# Sheet1.net
KiCad netlist of a schematic drawn in Altium Designer
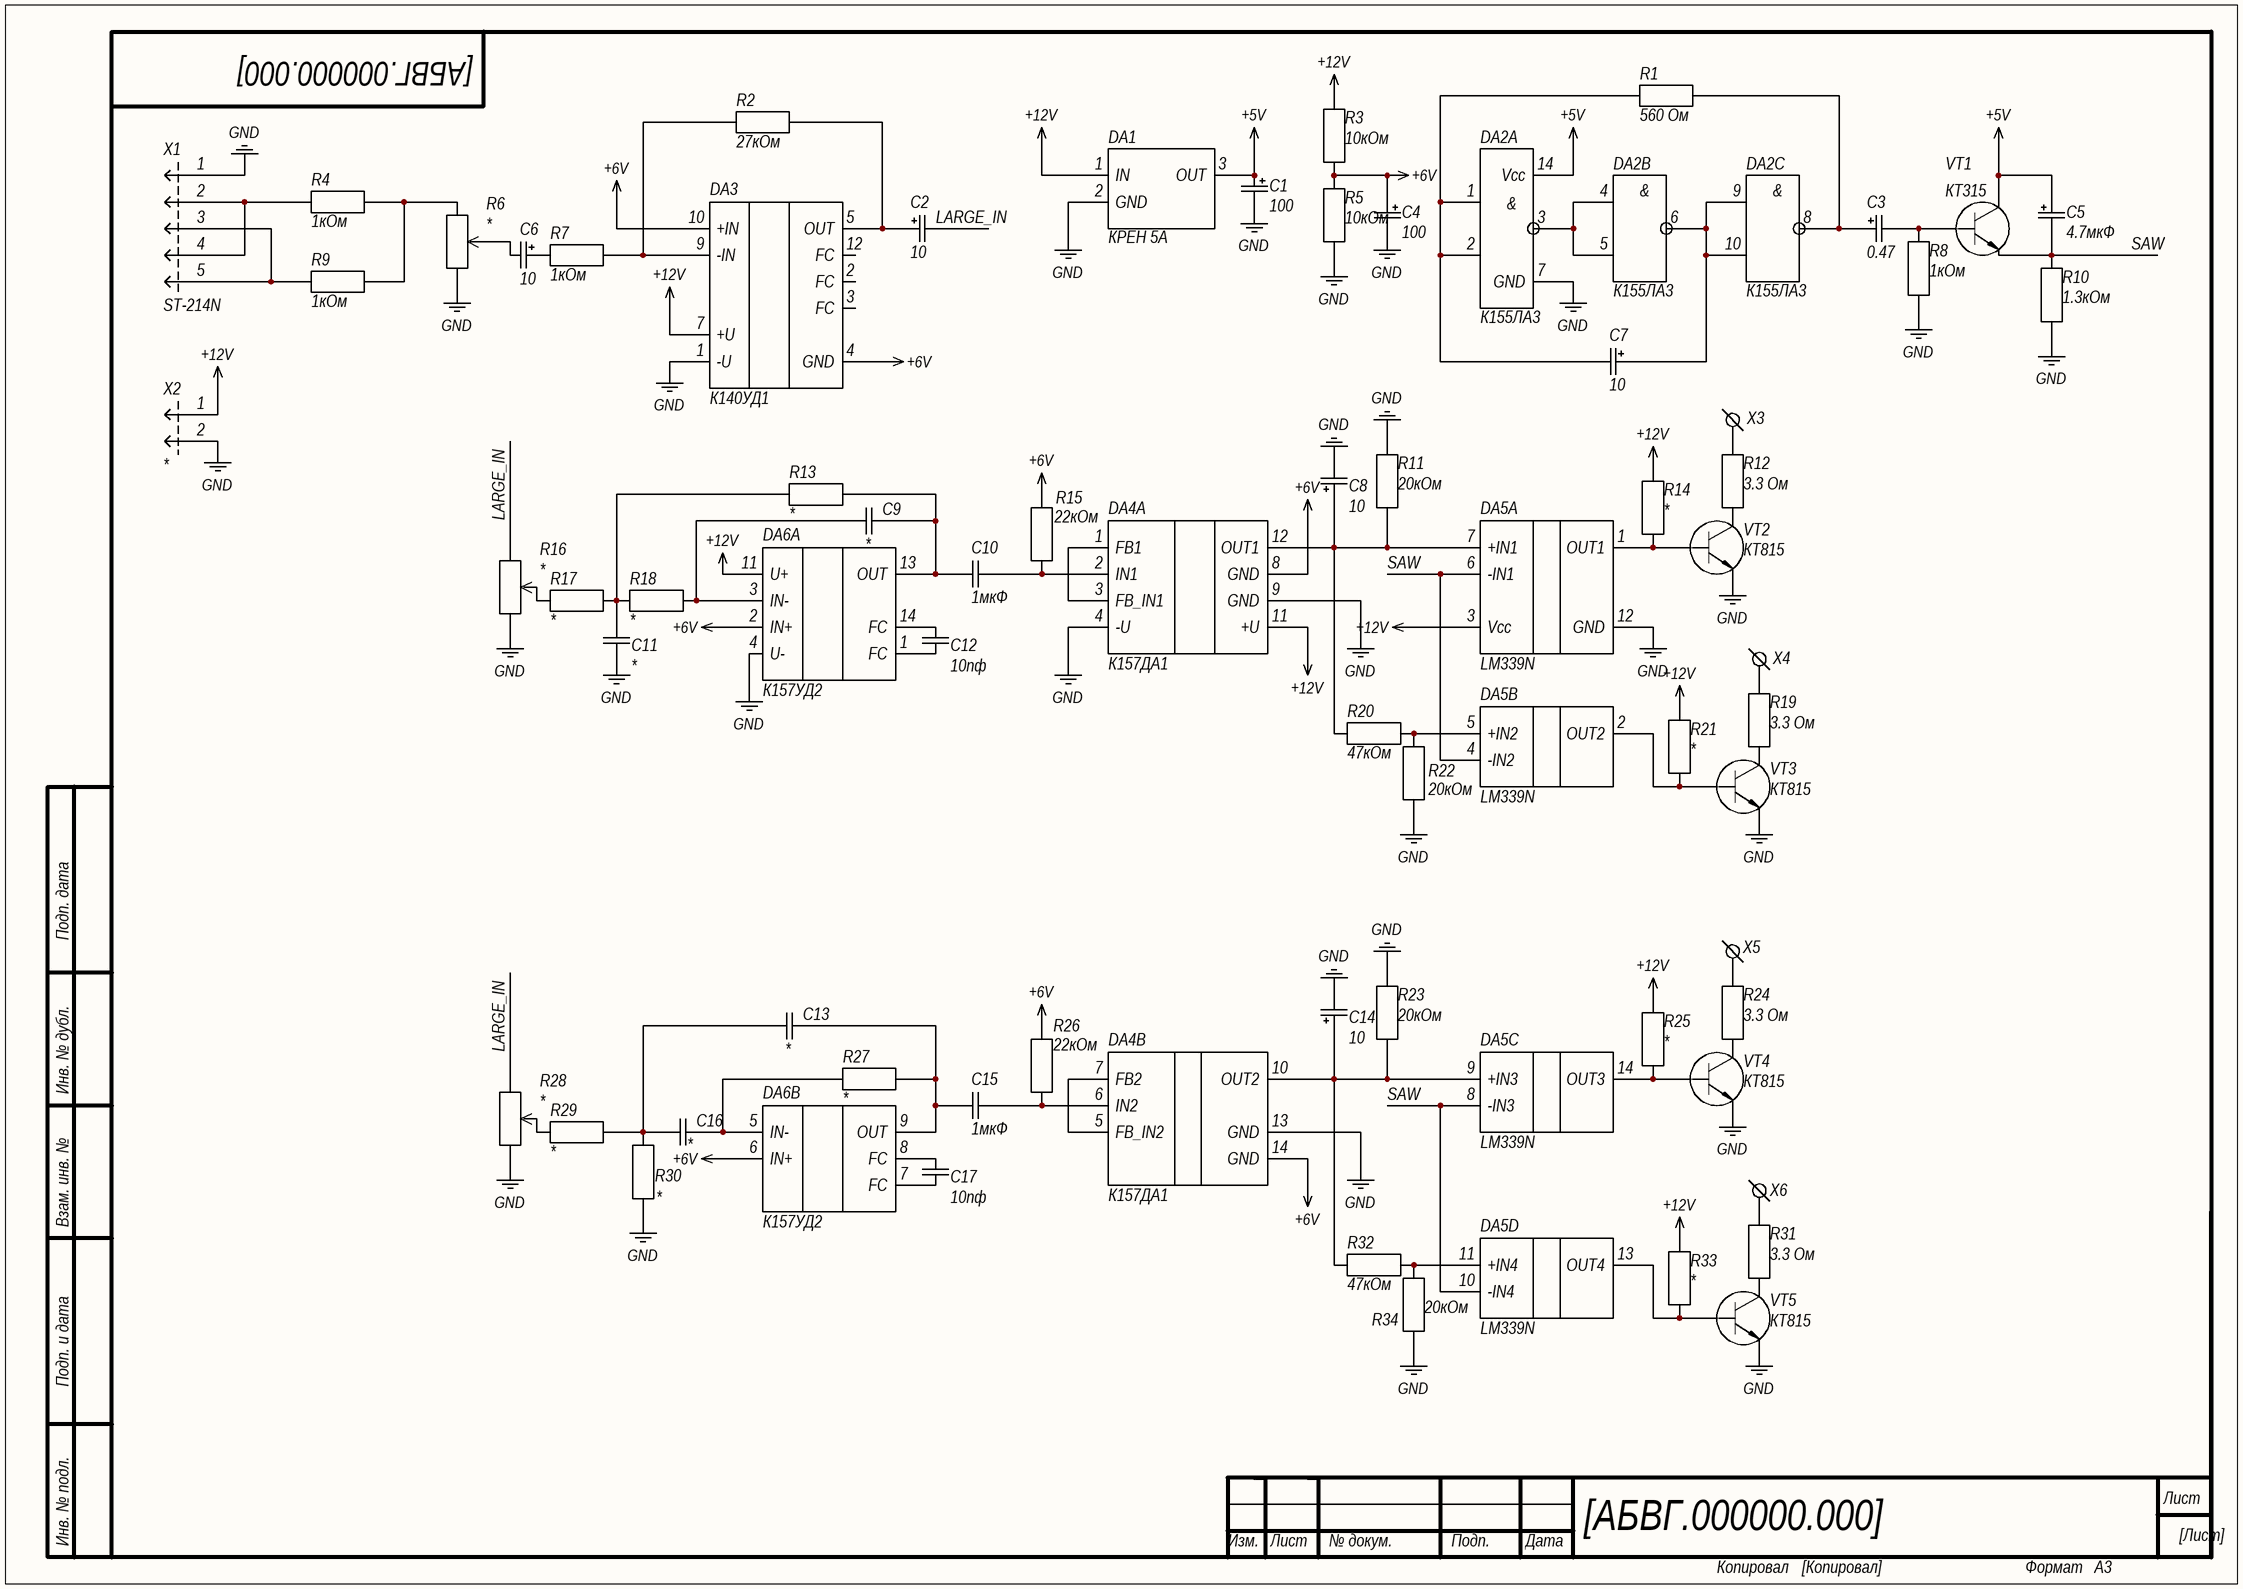
[diagram p0: Sheet1.SchDoc]

(export (version "E")
  (design (tool "Eeschema 10.0.6"))
  (components
    (comp (ref "C1") (value "100") (footprint "C 3.5mm") (libsource (lib "lib") (part "Capacitor Pol")))
    (comp (ref "C2") (value "10") (footprint "C 3.5mm") (libsource (lib "lib") (part "Capacitor Pol")))
    (comp (ref "C3") (value "0.47") (footprint "C 3.5mm") (libsource (lib "lib") (part "Capacitor Pol")))
    (comp (ref "C4") (value "100") (footprint "C 3.5mm") (libsource (lib "lib") (part "Capacitor Pol")))
    (comp (ref "C5") (value "4.7мкФ") (footprint "C 3.5mm") (libsource (lib "lib") (part "Capacitor Pol")))
    (comp (ref "C6") (value "10") (footprint "C 3.5mm") (libsource (lib "lib") (part "Capacitor Pol")))
    (comp (ref "C7") (value "10") (footprint "C 3.5mm") (libsource (lib "lib") (part "Capacitor Pol")))
    (comp (ref "C8") (value "10") (footprint "C 3.5mm") (libsource (lib "lib") (part "Capacitor Pol")))
    (comp (ref "C9") (value "*") (footprint "C 15mm") (libsource (lib "lib") (part "Capacitor")))
    (comp (ref "C10") (value "1мкФ") (footprint "C 10mm") (libsource (lib "lib") (part "Capacitor")))
    (comp (ref "C11") (value "*") (footprint "C 15mm") (libsource (lib "lib") (part "Capacitor")))
    (comp (ref "C12") (value "10пф") (footprint "C 10mm") (libsource (lib "lib") (part "Capacitor")))
    (comp (ref "C13") (value "*") (footprint "C 15mm") (libsource (lib "lib") (part "Capacitor")))
    (comp (ref "C14") (value "10") (footprint "C 3.5mm") (libsource (lib "lib") (part "Capacitor Pol")))
    (comp (ref "C15") (value "1мкФ") (footprint "C 10mm") (libsource (lib "lib") (part "Capacitor")))
    (comp (ref "C16") (value "*") (footprint "C 15mm") (libsource (lib "lib") (part "Capacitor")))
    (comp (ref "C17") (value "10пф") (footprint "C 10mm") (libsource (lib "lib") (part "Capacitor")))
    (comp (ref "DA1") (value "КРЕН 5А") (footprint "TO-220") (libsource (lib "lib") (part "KREN 5A")))
    (comp (ref "DA2") (value "К155ЛА3") (footprint "14-LEAD DIP") (libsource (lib "lib") (part "К155ЛА3")))
    (comp (ref "DA3") (value "К140УД1") (footprint "301.12-1") (libsource (lib "lib") (part "К140УД1")))
    (comp (ref "DA4") (value "К157ДА1") (footprint "14-LEAD DIP") (libsource (lib "lib") (part "К157ДА1")))
    (comp (ref "DA5") (value "LM339N") (footprint "14-LEAD DIP") (libsource (lib "lib") (part "LM339N")))
    (comp (ref "DA6") (value "К157УД2") (footprint "14-LEAD DIP") (libsource (lib "lib") (part "К157УД2")))
    (comp (ref "R1") (value "560 Ом") (footprint "R 10mm") (libsource (lib "") (part "Resistor_2")))
    (comp (ref "R2") (value "27кОм") (footprint "R 10mm") (libsource (lib "") (part "Resistor_2")))
    (comp (ref "R3") (value "10кОм") (footprint "R 10mm") (libsource (lib "") (part "Resistor_1")))
    (comp (ref "R4") (value "1кОм") (footprint "R 10mm") (libsource (lib "") (part "Resistor_2")))
    (comp (ref "R5") (value "10кОм") (footprint "R 10mm") (libsource (lib "") (part "Resistor_1")))
    (comp (ref "R6") (value "*") (footprint "OFF BOARD RESISTOR") (libsource (lib "") (part "ResistorVar_1")))
    (comp (ref "R7") (value "1кОм") (footprint "R 10mm") (libsource (lib "") (part "Resistor_2")))
    (comp (ref "R8") (value "1кОм") (footprint "R 10mm") (libsource (lib "") (part "Resistor_1")))
    (comp (ref "R9") (value "1кОм") (footprint "R 10mm") (libsource (lib "") (part "Resistor_2")))
    (comp (ref "R10") (value "1.3кОм") (footprint "R 10mm") (libsource (lib "") (part "Resistor_1")))
    (comp (ref "R11") (value "20кОм") (footprint "R 10mm") (libsource (lib "") (part "Resistor_1")))
    (comp (ref "R12") (value "3.3 Ом") (footprint "R 10mm") (libsource (lib "") (part "Resistor_1")))
    (comp (ref "R13") (value "*") (footprint "R 10mm") (libsource (lib "lib") (part "Resistor")))
    (comp (ref "R14") (value "*") (footprint "R 10mm") (libsource (lib "") (part "Resistor_1")))
    (comp (ref "R15") (value "22кОм") (footprint "R 10mm") (libsource (lib "") (part "Resistor_1")))
    (comp (ref "R16")
      (value "*")
      (footprint "OFF BOARD RESISTOR")
      (libsource (lib "lib") (part "ResistorVar"))
    )
    (comp (ref "R17") (value "*") (footprint "R 10mm") (libsource (lib "") (part "Resistor_2")))
    (comp (ref "R18") (value "*") (footprint "R 10mm") (libsource (lib "") (part "Resistor_2")))
    (comp (ref "R19") (value "3.3 Ом") (footprint "R 10mm") (libsource (lib "") (part "Resistor_1")))
    (comp (ref "R20") (value "47кОм") (footprint "R 10mm") (libsource (lib "") (part "Resistor_2")))
    (comp (ref "R21") (value "*") (footprint "R 10mm") (libsource (lib "") (part "Resistor_1")))
    (comp (ref "R22") (value "20кОм") (footprint "R 10mm") (libsource (lib "") (part "Resistor_1")))
    (comp (ref "R23") (value "20кОм") (footprint "R 10mm") (libsource (lib "") (part "Resistor_1")))
    (comp (ref "R24") (value "3.3 Ом") (footprint "R 10mm") (libsource (lib "") (part "Resistor_1")))
    (comp (ref "R25") (value "*") (footprint "R 10mm") (libsource (lib "") (part "Resistor_1")))
    (comp (ref "R26") (value "22кОм") (footprint "R 10mm") (libsource (lib "") (part "Resistor_1")))
    (comp (ref "R27") (value "*") (footprint "R 10mm") (libsource (lib "lib") (part "Resistor")))
    (comp (ref "R28")
      (value "*")
      (footprint "OFF BOARD RESISTOR")
      (libsource (lib "lib") (part "ResistorVar"))
    )
    (comp (ref "R29") (value "*") (footprint "R 10mm") (libsource (lib "") (part "Resistor_2")))
    (comp (ref "R30") (value "*") (footprint "R 10mm") (libsource (lib "") (part "Resistor_1")))
    (comp (ref "R31") (value "3.3 Ом") (footprint "R 10mm") (libsource (lib "") (part "Resistor_1")))
    (comp (ref "R32") (value "47кОм") (footprint "R 10mm") (libsource (lib "") (part "Resistor_2")))
    (comp (ref "R33") (value "*") (footprint "R 10mm") (libsource (lib "") (part "Resistor_1")))
    (comp (ref "R34") (value "20кОм") (footprint "R 10mm") (libsource (lib "") (part "Resistor_1")))
    (comp (ref "VT1")
      (value "КТ315")
      (footprint "KT-13")
      (description "Transistor")
      (libsource (lib "lib") (part "NPN"))
    )
    (comp (ref "VT2")
      (value "КТ815")
      (footprint "KT-27")
      (description "Transistor")
      (libsource (lib "lib") (part "NPN"))
    )
    (comp (ref "VT3")
      (value "КТ815")
      (footprint "KT-27")
      (description "Transistor")
      (libsource (lib "lib") (part "NPN"))
    )
    (comp (ref "VT4")
      (value "КТ815")
      (footprint "KT-27")
      (description "Transistor")
      (libsource (lib "lib") (part "NPN"))
    )
    (comp (ref "VT5")
      (value "КТ815")
      (footprint "KT-27")
      (description "Transistor")
      (libsource (lib "lib") (part "NPN"))
    )
    (comp (ref "X1")
      (value "ST-214N")
      (footprint "ST-214N")
      (description "Connector")
      (libsource (lib "lib") (part "ST-214N"))
    )
    (comp (ref "X2")
      (value "*")
      (footprint "PLS-2")
      (description "Connector")
      (libsource (lib "lib") (part "Connector 2-pin"))
    )
    (comp (ref "X3") (value "~") (footprint "TP 1,4mm") (libsource (lib "lib") (part "TP")))
    (comp (ref "X4") (value "~") (footprint "TP 1,4mm") (libsource (lib "lib") (part "TP")))
    (comp (ref "X5") (value "~") (footprint "TP 1,4mm") (libsource (lib "lib") (part "TP")))
    (comp (ref "X6") (value "~") (footprint "TP 1,4mm") (libsource (lib "lib") (part "TP")))
  )
  (nets
    (net (code "1") (name "+5V") (class "Default")
      (node (ref "C1") (pin "1") (pinfunction "1_1") (pintype "passive"))
      (node (ref "C5") (pin "1") (pinfunction "1_1") (pintype "passive"))
      (node (ref "DA1") (pin "3") (pinfunction "OUT_3") (pintype "power_in"))
      (node (ref "DA2") (pin "14") (pinfunction "Vcc_14") (pintype "power_in"))
      (node (ref "VT1") (pin "3") (pinfunction "3_3") (pintype "passive"))
    )
    (net (code "2") (name "+6V") (class "Default")
      (node (ref "C4") (pin "1") (pinfunction "1_1") (pintype "passive"))
      (node (ref "DA3") (pin "10") (pinfunction "+IN_10") (pintype "power_in"))
      (node (ref "DA3") (pin "4") (pinfunction "GND_4") (pintype "power_in"))
      (node (ref "DA4") (pin "14") (pinfunction "GND_14") (pintype "power_in"))
      (node (ref "DA4") (pin "8") (pinfunction "GND_8") (pintype "power_in"))
      (node (ref "DA6") (pin "2") (pinfunction "IN+_2") (pintype "power_in"))
      (node (ref "DA6") (pin "6") (pinfunction "IN+_6") (pintype "power_in"))
      (node (ref "R15") (pin "2") (pinfunction "2_2") (pintype "passive"))
      (node (ref "R26") (pin "2") (pinfunction "2_2") (pintype "passive"))
      (node (ref "R3") (pin "1") (pinfunction "1_1") (pintype "passive"))
      (node (ref "R5") (pin "2") (pinfunction "2_2") (pintype "passive"))
    )
    (net (code "3") (name "+12V") (class "Default")
      (node (ref "DA1") (pin "1") (pinfunction "IN_1") (pintype "power_in"))
      (node (ref "DA3") (pin "7") (pinfunction "+U_7") (pintype "power_in"))
      (node (ref "DA4") (pin "11") (pinfunction "+U_11") (pintype "power_in"))
      (node (ref "DA5") (pin "3") (pinfunction "Vcc_3") (pintype "power_in"))
      (node (ref "DA6") (pin "11") (pinfunction "U+_11") (pintype "power_in"))
      (node (ref "R14") (pin "2") (pinfunction "2_2") (pintype "passive"))
      (node (ref "R21") (pin "2") (pinfunction "2_2") (pintype "passive"))
      (node (ref "R25") (pin "2") (pinfunction "2_2") (pintype "passive"))
      (node (ref "R3") (pin "2") (pinfunction "2_2") (pintype "passive"))
      (node (ref "R33") (pin "2") (pinfunction "2_2") (pintype "passive"))
      (node (ref "X2") (pin "1") (pinfunction "1_1") (pintype "power_in"))
    )
    (net (code "4") (name "/LARGE_IN") (class "Default")
      (node (ref "C2") (pin "2") (pinfunction "2_2") (pintype "passive"))
      (node (ref "R16") (pin "1") (pinfunction "1_1") (pintype "passive"))
      (node (ref "R28") (pin "1") (pinfunction "1_1") (pintype "passive"))
    )
    (net (code "5") (name "/SAW") (class "Default")
      (node (ref "C5") (pin "2") (pinfunction "2_2") (pintype "passive"))
      (node (ref "DA5") (pin "10") (pinfunction "-IN4_10") (pintype "power_in"))
      (node (ref "DA5") (pin "4") (pinfunction "-IN2_4") (pintype "power_in"))
      (node (ref "DA5") (pin "6") (pinfunction "-IN1_6") (pintype "power_in"))
      (node (ref "DA5") (pin "8") (pinfunction "-IN3_8") (pintype "power_in"))
      (node (ref "R10") (pin "2") (pinfunction "2_2") (pintype "passive"))
      (node (ref "VT1") (pin "2") (pinfunction "2_2") (pintype "passive"))
    )
    (net (code "6") (name "GND") (class "Default")
      (node (ref "C1") (pin "2") (pinfunction "2_2") (pintype "passive"))
      (node (ref "C11") (pin "1") (pinfunction "1_1") (pintype "passive"))
      (node (ref "C14") (pin "2") (pinfunction "2_2") (pintype "passive"))
      (node (ref "C4") (pin "2") (pinfunction "2_2") (pintype "passive"))
      (node (ref "C8") (pin "2") (pinfunction "2_2") (pintype "passive"))
      (node (ref "DA1") (pin "2") (pinfunction "GND_2") (pintype "power_in"))
      (node (ref "DA2") (pin "7") (pinfunction "GND_7") (pintype "power_in"))
      (node (ref "DA3") (pin "1") (pinfunction "-U_1") (pintype "power_in"))
      (node (ref "DA4") (pin "13") (pinfunction "GND_13") (pintype "power_in"))
      (node (ref "DA4") (pin "4") (pinfunction "-U_4") (pintype "power_in"))
      (node (ref "DA4") (pin "9") (pinfunction "GND_9") (pintype "power_in"))
      (node (ref "DA5") (pin "12") (pinfunction "GND_12") (pintype "power_in"))
      (node (ref "DA6") (pin "4") (pinfunction "U-_4") (pintype "power_in"))
      (node (ref "R10") (pin "1") (pinfunction "1_1") (pintype "passive"))
      (node (ref "R11") (pin "2") (pinfunction "2_2") (pintype "passive"))
      (node (ref "R16") (pin "2") (pinfunction "2_2") (pintype "passive"))
      (node (ref "R22") (pin "1") (pinfunction "1_1") (pintype "passive"))
      (node (ref "R23") (pin "2") (pinfunction "2_2") (pintype "passive"))
      (node (ref "R28") (pin "2") (pinfunction "2_2") (pintype "passive"))
      (node (ref "R30") (pin "1") (pinfunction "1_1") (pintype "passive"))
      (node (ref "R34") (pin "1") (pinfunction "1_1") (pintype "passive"))
      (node (ref "R5") (pin "1") (pinfunction "1_1") (pintype "passive"))
      (node (ref "R6") (pin "1") (pinfunction "1_1") (pintype "passive"))
      (node (ref "R8") (pin "1") (pinfunction "1_1") (pintype "passive"))
      (node (ref "VT2") (pin "2") (pinfunction "2_2") (pintype "passive"))
      (node (ref "VT3") (pin "2") (pinfunction "2_2") (pintype "passive"))
      (node (ref "VT4") (pin "2") (pinfunction "2_2") (pintype "passive"))
      (node (ref "VT5") (pin "2") (pinfunction "2_2") (pintype "passive"))
      (node (ref "X1") (pin "1") (pinfunction "1_1") (pintype "power_in"))
      (node (ref "X2") (pin "2") (pinfunction "2_2") (pintype "power_in"))
    )
    (net (code "7") (name "Net-(C3-Pad2)") (class "Default")
      (node (ref "C3") (pin "2") (pinfunction "2_2") (pintype "passive"))
      (node (ref "R8") (pin "2") (pinfunction "2_2") (pintype "passive"))
      (node (ref "VT1") (pin "1") (pinfunction "1_1") (pintype "passive"))
    )
    (net (code "8") (name "Net-(C6-Pad1)") (class "Default")
      (node (ref "C6") (pin "1") (pinfunction "1_1") (pintype "passive"))
      (node (ref "R7") (pin "1") (pinfunction "1_1") (pintype "passive"))
    )
    (net (code "9") (name "Net-(C6-Pad2)") (class "Default")
      (node (ref "C6") (pin "2") (pinfunction "2_2") (pintype "passive"))
      (node (ref "R6") (pin "3") (pinfunction "3_3") (pintype "power_in"))
    )
    (net (code "10") (name "Net-(C11-Pad2)") (class "Default")
      (node (ref "C11") (pin "2") (pinfunction "2_2") (pintype "passive"))
      (node (ref "R13") (pin "2") (pinfunction "2_2") (pintype "passive"))
      (node (ref "R17") (pin "2") (pinfunction "2_2") (pintype "passive"))
      (node (ref "R18") (pin "1") (pinfunction "1_1") (pintype "passive"))
    )
    (net (code "11") (name "Net-(C12-Pad1)") (class "Default")
      (node (ref "C12") (pin "1") (pinfunction "1_1") (pintype "passive"))
      (node (ref "DA6") (pin "1") (pinfunction "FC_1") (pintype "power_in"))
    )
    (net (code "12") (name "Net-(C12-Pad2)") (class "Default")
      (node (ref "C12") (pin "2") (pinfunction "2_2") (pintype "passive"))
      (node (ref "DA6") (pin "14") (pinfunction "FC_14") (pintype "power_in"))
    )
    (net (code "13") (name "Net-(C13-Pad1)") (class "Default")
      (node (ref "C13") (pin "1") (pinfunction "1_1") (pintype "passive"))
      (node (ref "C16") (pin "1") (pinfunction "1_1") (pintype "passive"))
      (node (ref "R29") (pin "2") (pinfunction "2_2") (pintype "passive"))
      (node (ref "R30") (pin "2") (pinfunction "2_2") (pintype "passive"))
    )
    (net (code "14") (name "Net-(C17-Pad1)") (class "Default")
      (node (ref "C17") (pin "1") (pinfunction "1_1") (pintype "passive"))
      (node (ref "DA6") (pin "7") (pinfunction "FC_7") (pintype "power_in"))
    )
    (net (code "15") (name "Net-(C17-Pad2)") (class "Default")
      (node (ref "C17") (pin "2") (pinfunction "2_2") (pintype "passive"))
      (node (ref "DA6") (pin "8") (pinfunction "FC_8") (pintype "power_in"))
    )
    (net (code "16") (name "Net-(DA2A-10)") (class "Default")
      (node (ref "C7") (pin "2") (pinfunction "2_2") (pintype "passive"))
      (node (ref "DA2") (pin "1") (pinfunction "9_1") (pintype "power_in"))
      (node (ref "DA2") (pin "2") (pinfunction "10_2") (pintype "power_in"))
      (node (ref "R1") (pin "1") (pinfunction "1_1") (pintype "passive"))
    )
    (net (code "17") (name "Net-(DA2A-11)") (class "Default")
      (node (ref "DA2") (pin "3") (pinfunction "11_3") (pintype "power_in"))
      (node (ref "DA2") (pin "4") (pinfunction "12_4") (pintype "power_in"))
      (node (ref "DA2") (pin "5") (pinfunction "13_5") (pintype "power_in"))
    )
    (net (code "18") (name "Net-(DA2B-14)") (class "Default")
      (node (ref "C7") (pin "1") (pinfunction "1_1") (pintype "passive"))
      (node (ref "DA2") (pin "10") (pinfunction "18_10") (pintype "power_in"))
      (node (ref "DA2") (pin "6") (pinfunction "14_6") (pintype "power_in"))
      (node (ref "DA2") (pin "9") (pinfunction "17_9") (pintype "power_in"))
    )
    (net (code "19") (name "Net-(DA2C-16)") (class "Default")
      (node (ref "C3") (pin "1") (pinfunction "1_1") (pintype "passive"))
      (node (ref "DA2") (pin "8") (pinfunction "16_8") (pintype "power_in"))
      (node (ref "R1") (pin "2") (pinfunction "2_2") (pintype "passive"))
    )
    (net (code "20") (name "Net-(DA3--IN)") (class "Default")
      (node (ref "DA3") (pin "9") (pinfunction "-IN_9") (pintype "power_in"))
      (node (ref "R2") (pin "1") (pinfunction "1_1") (pintype "passive"))
      (node (ref "R7") (pin "2") (pinfunction "2_2") (pintype "passive"))
    )
    (net (code "21") (name "Net-(DA3-OUT)") (class "Default")
      (node (ref "C2") (pin "1") (pinfunction "1_1") (pintype "passive"))
      (node (ref "DA3") (pin "5") (pinfunction "OUT_5") (pintype "power_in"))
      (node (ref "R2") (pin "2") (pinfunction "2_2") (pintype "passive"))
    )
    (net (code "22") (name "Net-(DA4A-FB1)") (class "Default")
      (node (ref "DA4") (pin "1") (pinfunction "FB1_1") (pintype "power_in"))
      (node (ref "DA4") (pin "3") (pinfunction "FB_IN1_3") (pintype "power_in"))
    )
    (net (code "23") (name "Net-(DA4A-IN1)") (class "Default")
      (node (ref "C10") (pin "2") (pinfunction "2_2") (pintype "passive"))
      (node (ref "DA4") (pin "2") (pinfunction "IN1_2") (pintype "power_in"))
      (node (ref "R15") (pin "1") (pinfunction "1_1") (pintype "passive"))
    )
    (net (code "24") (name "Net-(DA4A-OUT1)") (class "Default")
      (node (ref "C8") (pin "1") (pinfunction "1_1") (pintype "passive"))
      (node (ref "DA4") (pin "12") (pinfunction "OUT1_12") (pintype "power_in"))
      (node (ref "DA5") (pin "7") (pinfunction "+IN1_7") (pintype "power_in"))
      (node (ref "R11") (pin "1") (pinfunction "1_1") (pintype "passive"))
      (node (ref "R20") (pin "1") (pinfunction "1_1") (pintype "passive"))
    )
    (net (code "25") (name "Net-(DA4B-FB2)") (class "Default")
      (node (ref "DA4") (pin "5") (pinfunction "FB_IN2_5") (pintype "power_in"))
      (node (ref "DA4") (pin "7") (pinfunction "FB2_7") (pintype "power_in"))
    )
    (net (code "26") (name "Net-(DA4B-IN2)") (class "Default")
      (node (ref "C15") (pin "2") (pinfunction "2_2") (pintype "passive"))
      (node (ref "DA4") (pin "6") (pinfunction "IN2_6") (pintype "power_in"))
      (node (ref "R26") (pin "1") (pinfunction "1_1") (pintype "passive"))
    )
    (net (code "27") (name "Net-(DA4B-OUT2)") (class "Default")
      (node (ref "C14") (pin "1") (pinfunction "1_1") (pintype "passive"))
      (node (ref "DA4") (pin "10") (pinfunction "OUT2_10") (pintype "power_in"))
      (node (ref "DA5") (pin "9") (pinfunction "+IN3_9") (pintype "power_in"))
      (node (ref "R23") (pin "1") (pinfunction "1_1") (pintype "passive"))
      (node (ref "R32") (pin "1") (pinfunction "1_1") (pintype "passive"))
    )
    (net (code "28") (name "Net-(DA5A-OUT1)") (class "Default")
      (node (ref "DA5") (pin "1") (pinfunction "OUT1_1") (pintype "power_in"))
      (node (ref "R14") (pin "1") (pinfunction "1_1") (pintype "passive"))
      (node (ref "VT2") (pin "1") (pinfunction "1_1") (pintype "passive"))
    )
    (net (code "29") (name "Net-(DA5B-+IN2)") (class "Default")
      (node (ref "DA5") (pin "5") (pinfunction "+IN2_5") (pintype "power_in"))
      (node (ref "R20") (pin "2") (pinfunction "2_2") (pintype "passive"))
      (node (ref "R22") (pin "2") (pinfunction "2_2") (pintype "passive"))
    )
    (net (code "30") (name "Net-(DA5B-OUT2)") (class "Default")
      (node (ref "DA5") (pin "2") (pinfunction "OUT2_2") (pintype "power_in"))
      (node (ref "R21") (pin "1") (pinfunction "1_1") (pintype "passive"))
      (node (ref "VT3") (pin "1") (pinfunction "1_1") (pintype "passive"))
    )
    (net (code "31") (name "Net-(DA5C-OUT3)") (class "Default")
      (node (ref "DA5") (pin "14") (pinfunction "OUT3_14") (pintype "power_in"))
      (node (ref "R25") (pin "1") (pinfunction "1_1") (pintype "passive"))
      (node (ref "VT4") (pin "1") (pinfunction "1_1") (pintype "passive"))
    )
    (net (code "32") (name "Net-(DA5D-+IN4)") (class "Default")
      (node (ref "DA5") (pin "11") (pinfunction "+IN4_11") (pintype "power_in"))
      (node (ref "R32") (pin "2") (pinfunction "2_2") (pintype "passive"))
      (node (ref "R34") (pin "2") (pinfunction "2_2") (pintype "passive"))
    )
    (net (code "33") (name "Net-(DA5D-OUT4)") (class "Default")
      (node (ref "DA5") (pin "13") (pinfunction "OUT4_13") (pintype "power_in"))
      (node (ref "R33") (pin "1") (pinfunction "1_1") (pintype "passive"))
      (node (ref "VT5") (pin "1") (pinfunction "1_1") (pintype "passive"))
    )
    (net (code "34") (name "Net-(DA6A-IN-)") (class "Default")
      (node (ref "C9") (pin "1") (pinfunction "1_1") (pintype "passive"))
      (node (ref "DA6") (pin "3") (pinfunction "IN-_3") (pintype "power_in"))
      (node (ref "R18") (pin "2") (pinfunction "2_2") (pintype "passive"))
    )
    (net (code "35") (name "Net-(DA6A-OUT)") (class "Default")
      (node (ref "C10") (pin "1") (pinfunction "1_1") (pintype "passive"))
      (node (ref "C9") (pin "2") (pinfunction "2_2") (pintype "passive"))
      (node (ref "DA6") (pin "13") (pinfunction "OUT_13") (pintype "power_in"))
      (node (ref "R13") (pin "1") (pinfunction "1_1") (pintype "passive"))
    )
    (net (code "36") (name "Net-(DA6B-IN-)") (class "Default")
      (node (ref "C16") (pin "2") (pinfunction "2_2") (pintype "passive"))
      (node (ref "DA6") (pin "5") (pinfunction "IN-_5") (pintype "power_in"))
      (node (ref "R27") (pin "2") (pinfunction "2_2") (pintype "passive"))
    )
    (net (code "37") (name "Net-(DA6B-OUT)") (class "Default")
      (node (ref "C13") (pin "2") (pinfunction "2_2") (pintype "passive"))
      (node (ref "C15") (pin "1") (pinfunction "1_1") (pintype "passive"))
      (node (ref "DA6") (pin "9") (pinfunction "OUT_9") (pintype "power_in"))
      (node (ref "R27") (pin "1") (pinfunction "1_1") (pintype "passive"))
    )
    (net (code "38") (name "Net-(R4-Pad1)") (class "Default")
      (node (ref "R4") (pin "1") (pinfunction "1_1") (pintype "passive"))
      (node (ref "X1") (pin "2") (pinfunction "2_2") (pintype "power_in"))
      (node (ref "X1") (pin "4") (pinfunction "4_4") (pintype "power_in"))
    )
    (net (code "39") (name "Net-(R4-Pad2)") (class "Default")
      (node (ref "R4") (pin "2") (pinfunction "2_2") (pintype "passive"))
      (node (ref "R6") (pin "2") (pinfunction "2_2") (pintype "passive"))
      (node (ref "R9") (pin "2") (pinfunction "2_2") (pintype "passive"))
    )
    (net (code "40") (name "Net-(R9-Pad1)") (class "Default")
      (node (ref "R9") (pin "1") (pinfunction "1_1") (pintype "passive"))
      (node (ref "X1") (pin "3") (pinfunction "3_3") (pintype "power_in"))
      (node (ref "X1") (pin "5") (pinfunction "5_5") (pintype "power_in"))
    )
    (net (code "41") (name "Net-(R12-Pad1)") (class "Default")
      (node (ref "R12") (pin "1") (pinfunction "1_1") (pintype "passive"))
      (node (ref "VT2") (pin "3") (pinfunction "3_3") (pintype "passive"))
    )
    (net (code "42") (name "Net-(R12-Pad2)") (class "Default")
      (node (ref "R12") (pin "2") (pinfunction "2_2") (pintype "passive"))
      (node (ref "X3") (pin "1") (pinfunction "1_1") (pintype "power_in"))
    )
    (net (code "43") (name "Net-(R16-Pad3)") (class "Default")
      (node (ref "R16") (pin "3") (pinfunction "3_3") (pintype "power_in"))
      (node (ref "R17") (pin "1") (pinfunction "1_1") (pintype "passive"))
    )
    (net (code "44") (name "Net-(R19-Pad1)") (class "Default")
      (node (ref "R19") (pin "1") (pinfunction "1_1") (pintype "passive"))
      (node (ref "VT3") (pin "3") (pinfunction "3_3") (pintype "passive"))
    )
    (net (code "45") (name "Net-(R19-Pad2)") (class "Default")
      (node (ref "R19") (pin "2") (pinfunction "2_2") (pintype "passive"))
      (node (ref "X4") (pin "1") (pinfunction "1_1") (pintype "power_in"))
    )
    (net (code "46") (name "Net-(R24-Pad1)") (class "Default")
      (node (ref "R24") (pin "1") (pinfunction "1_1") (pintype "passive"))
      (node (ref "VT4") (pin "3") (pinfunction "3_3") (pintype "passive"))
    )
    (net (code "47") (name "Net-(R24-Pad2)") (class "Default")
      (node (ref "R24") (pin "2") (pinfunction "2_2") (pintype "passive"))
      (node (ref "X5") (pin "1") (pinfunction "1_1") (pintype "power_in"))
    )
    (net (code "48") (name "Net-(R28-Pad3)") (class "Default")
      (node (ref "R28") (pin "3") (pinfunction "3_3") (pintype "power_in"))
      (node (ref "R29") (pin "1") (pinfunction "1_1") (pintype "passive"))
    )
    (net (code "49") (name "Net-(R31-Pad1)") (class "Default")
      (node (ref "R31") (pin "1") (pinfunction "1_1") (pintype "passive"))
      (node (ref "VT5") (pin "3") (pinfunction "3_3") (pintype "passive"))
    )
    (net (code "50") (name "Net-(R31-Pad2)") (class "Default")
      (node (ref "R31") (pin "2") (pinfunction "2_2") (pintype "passive"))
      (node (ref "X6") (pin "1") (pinfunction "1_1") (pintype "power_in"))
    )
    (net (code "51") (name "unconnected-(DA3-FC-Pad2)") (class "Default")
      (node (ref "DA3") (pin "2") (pinfunction "FC_2") (pintype "power_in"))
    )
    (net (code "52") (name "unconnected-(DA3-FC-Pad3)") (class "Default")
      (node (ref "DA3") (pin "3") (pinfunction "FC_3") (pintype "power_in"))
    )
    (net (code "53") (name "unconnected-(DA3-FC-Pad12)") (class "Default")
      (node (ref "DA3") (pin "12") (pinfunction "FC_12") (pintype "power_in"))
    )
  )
)
